# 06_Data_IN_OUT.net
KiCad netlist of a schematic drawn in Altium Designer
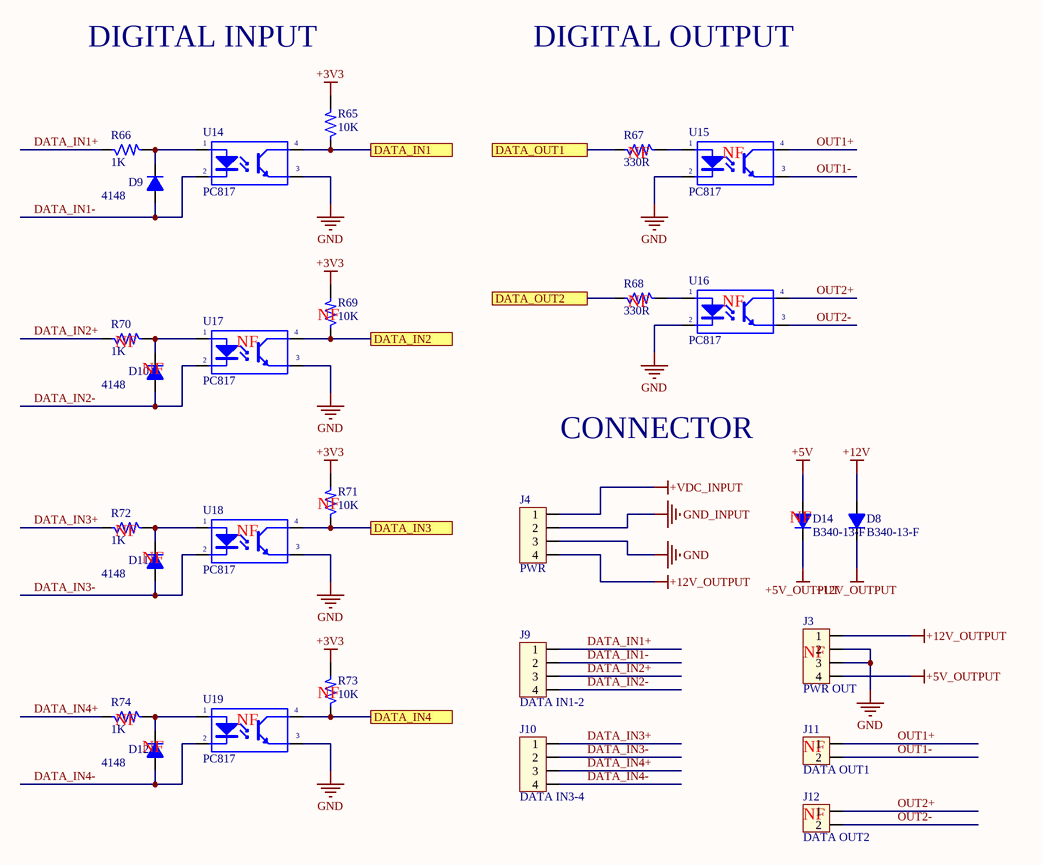
[diagram p0: [06] Data IN_OUT.SchDoc]

(export (version "E")
  (design (tool "Eeschema 10.0.6"))
  (components
    (comp (ref "D8")
      (value "B340-13-F")
      (footprint "DO-214AB SMA")
      (description "Diode 1A")
      (libsource (lib "khapham") (part "D1A"))
    )
    (comp (ref "D9")
      (value "4148")
      (footprint "DO-4148 SMD")
      (description "Diode 1A")
      (libsource (lib "khapham") (part "D1A"))
    )
    (comp (ref "D10")
      (value "4148")
      (footprint "DO-4148 SMD")
      (description "Diode 1A")
      (libsource (lib "khapham") (part "D1A"))
    )
    (comp (ref "D11")
      (value "4148")
      (footprint "DO-4148 SMD")
      (description "Diode 1A")
      (libsource (lib "khapham") (part "D1A"))
    )
    (comp (ref "D12")
      (value "4148")
      (footprint "DO-4148 SMD")
      (description "Diode 1A")
      (libsource (lib "khapham") (part "D1A"))
    )
    (comp (ref "D14")
      (value "B340-13-F")
      (footprint "DO-214AB SMA")
      (description "Diode 1A")
      (libsource (lib "khapham") (part "D1A"))
    )
    (comp (ref "J3")
      (value "PWR OUT")
      (footprint "CON_2.54mm_4")
      (description "Connector 4")
      (libsource (lib "khapham") (part "Con4"))
    )
    (comp (ref "J4")
      (value "PWR")
      (footprint "Hed4V_3.96")
      (description "Header 4 (Green)")
      (libsource (lib "khapham") (part "Hed4"))
    )
    (comp (ref "J9")
      (value "DATA IN1-2")
      (footprint "CON_2.54mm_4")
      (description "Connector 4")
      (libsource (lib "khapham") (part "Con4"))
    )
    (comp (ref "J10")
      (value "DATA IN3-4")
      (footprint "CON_2.54mm_4")
      (description "Connector 4")
      (libsource (lib "khapham") (part "Con4"))
    )
    (comp (ref "J11")
      (value "DATA OUT1")
      (footprint "CON_2.54mm_2")
      (description "Connector 2")
      (libsource (lib "khapham") (part "Con2"))
    )
    (comp (ref "J12")
      (value "DATA OUT2")
      (footprint "CON_2.54mm_2")
      (description "Connector 2")
      (libsource (lib "khapham") (part "Con2"))
    )
    (comp (ref "R65")
      (value "10K")
      (footprint "R0603 -SMT")
      (description "Resistor SMD")
      (libsource (lib "khapham") (part "RM"))
    )
    (comp (ref "R66")
      (value "1K")
      (footprint "R0603 -SMT")
      (description "Resistor SMD")
      (libsource (lib "khapham") (part "RM"))
    )
    (comp (ref "R67")
      (value "330R")
      (footprint "R0603 -SMT")
      (description "Resistor SMD")
      (libsource (lib "khapham") (part "RM"))
    )
    (comp (ref "R68")
      (value "330R")
      (footprint "R0603 -SMT")
      (description "Resistor SMD")
      (libsource (lib "khapham") (part "RM"))
    )
    (comp (ref "R69")
      (value "10K")
      (footprint "R0603 -SMT")
      (description "Resistor SMD")
      (libsource (lib "khapham") (part "RM"))
    )
    (comp (ref "R70")
      (value "1K")
      (footprint "R0603 -SMT")
      (description "Resistor SMD")
      (libsource (lib "khapham") (part "RM"))
    )
    (comp (ref "R71")
      (value "10K")
      (footprint "R0603 -SMT")
      (description "Resistor SMD")
      (libsource (lib "khapham") (part "RM"))
    )
    (comp (ref "R72")
      (value "1K")
      (footprint "R0603 -SMT")
      (description "Resistor SMD")
      (libsource (lib "khapham") (part "RM"))
    )
    (comp (ref "R73")
      (value "10K")
      (footprint "R0603 -SMT")
      (description "Resistor SMD")
      (libsource (lib "khapham") (part "RM"))
    )
    (comp (ref "R74")
      (value "1K")
      (footprint "R0603 -SMT")
      (description "Resistor SMD")
      (libsource (lib "khapham") (part "RM"))
    )
    (comp (ref "U14")
      (value "PC817")
      (footprint "DIP4/W0.3")
      (description "Single Opto")
      (libsource (lib "khapham") (part "PC817"))
    )
    (comp (ref "U15")
      (value "PC817")
      (footprint "DIP4/W0.3")
      (description "Single Opto")
      (libsource (lib "khapham") (part "PC817"))
    )
    (comp (ref "U16")
      (value "PC817")
      (footprint "DIP4/W0.3")
      (description "Single Opto")
      (libsource (lib "khapham") (part "PC817"))
    )
    (comp (ref "U17")
      (value "PC817")
      (footprint "DIP4/W0.3")
      (description "Single Opto")
      (libsource (lib "khapham") (part "PC817"))
    )
    (comp (ref "U18")
      (value "PC817")
      (footprint "DIP4/W0.3")
      (description "Single Opto")
      (libsource (lib "khapham") (part "PC817"))
    )
    (comp (ref "U19")
      (value "PC817")
      (footprint "DIP4/W0.3")
      (description "Single Opto")
      (libsource (lib "khapham") (part "PC817"))
    )
  )
  (nets
    (net (code "1") (name "+3V3") (class "Default")
      (node (ref "R65") (pin "2") (pinfunction "2_2") (pintype "passive"))
      (node (ref "R69") (pin "2") (pinfunction "2_2") (pintype "passive"))
      (node (ref "R71") (pin "2") (pinfunction "2_2") (pintype "passive"))
      (node (ref "R73") (pin "2") (pinfunction "2_2") (pintype "passive"))
    )
    (net (code "2") (name "+5V") (class "Default")
      (node (ref "D14") (pin "1") (pinfunction "A_1") (pintype "passive"))
    )
    (net (code "3") (name "+5V_OUTPUT") (class "Default")
      (node (ref "D14") (pin "2") (pinfunction "K_2") (pintype "passive"))
      (node (ref "J3") (pin "4") (pinfunction "4_4") (pintype "passive"))
    )
    (net (code "4") (name "+12V") (class "Default")
      (node (ref "D8") (pin "1") (pinfunction "A_1") (pintype "passive"))
    )
    (net (code "5") (name "+12V_OUTPUT") (class "Default")
      (node (ref "D8") (pin "2") (pinfunction "K_2") (pintype "passive"))
      (node (ref "J3") (pin "1") (pinfunction "1_1") (pintype "passive"))
      (node (ref "J4") (pin "4") (pinfunction "4_4") (pintype "passive"))
    )
    (net (code "6") (name "+VDC_INPUT") (class "Default")
      (node (ref "J4") (pin "1") (pinfunction "1_1") (pintype "passive"))
    )
    (net (code "7") (name "/DATA_IN1") (class "Default")
      (node (ref "R65") (pin "1") (pinfunction "1_1") (pintype "passive"))
      (node (ref "U14") (pin "4") (pinfunction "C_4") (pintype "passive"))
    )
    (net (code "8") (name "/DATA_IN1+") (class "Default")
      (node (ref "J9") (pin "1") (pinfunction "1_1") (pintype "passive"))
      (node (ref "R66") (pin "1") (pinfunction "1_1") (pintype "passive"))
    )
    (net (code "9") (name "/DATA_IN1-") (class "Default")
      (node (ref "D9") (pin "1") (pinfunction "A_1") (pintype "passive"))
      (node (ref "J9") (pin "2") (pinfunction "2_2") (pintype "passive"))
      (node (ref "U14") (pin "2") (pinfunction "K_2") (pintype "passive"))
    )
    (net (code "10") (name "/DATA_IN2") (class "Default")
      (node (ref "R69") (pin "1") (pinfunction "1_1") (pintype "passive"))
      (node (ref "U17") (pin "4") (pinfunction "C_4") (pintype "passive"))
    )
    (net (code "11") (name "/DATA_IN2+") (class "Default")
      (node (ref "J9") (pin "3") (pinfunction "3_3") (pintype "passive"))
      (node (ref "R70") (pin "1") (pinfunction "1_1") (pintype "passive"))
    )
    (net (code "12") (name "/DATA_IN2-") (class "Default")
      (node (ref "D10") (pin "1") (pinfunction "A_1") (pintype "passive"))
      (node (ref "J9") (pin "4") (pinfunction "4_4") (pintype "passive"))
      (node (ref "U17") (pin "2") (pinfunction "K_2") (pintype "passive"))
    )
    (net (code "13") (name "/DATA_IN3") (class "Default")
      (node (ref "R71") (pin "1") (pinfunction "1_1") (pintype "passive"))
      (node (ref "U18") (pin "4") (pinfunction "C_4") (pintype "passive"))
    )
    (net (code "14") (name "/DATA_IN3+") (class "Default")
      (node (ref "J10") (pin "1") (pinfunction "1_1") (pintype "passive"))
      (node (ref "R72") (pin "1") (pinfunction "1_1") (pintype "passive"))
    )
    (net (code "15") (name "/DATA_IN3-") (class "Default")
      (node (ref "D11") (pin "1") (pinfunction "A_1") (pintype "passive"))
      (node (ref "J10") (pin "2") (pinfunction "2_2") (pintype "passive"))
      (node (ref "U18") (pin "2") (pinfunction "K_2") (pintype "passive"))
    )
    (net (code "16") (name "/DATA_IN4") (class "Default")
      (node (ref "R73") (pin "1") (pinfunction "1_1") (pintype "passive"))
      (node (ref "U19") (pin "4") (pinfunction "C_4") (pintype "passive"))
    )
    (net (code "17") (name "/DATA_IN4+") (class "Default")
      (node (ref "J10") (pin "3") (pinfunction "3_3") (pintype "passive"))
      (node (ref "R74") (pin "1") (pinfunction "1_1") (pintype "passive"))
    )
    (net (code "18") (name "/DATA_IN4-") (class "Default")
      (node (ref "D12") (pin "1") (pinfunction "A_1") (pintype "passive"))
      (node (ref "J10") (pin "4") (pinfunction "4_4") (pintype "passive"))
      (node (ref "U19") (pin "2") (pinfunction "K_2") (pintype "passive"))
    )
    (net (code "19") (name "/DATA_OUT1") (class "Default")
      (node (ref "R67") (pin "1") (pinfunction "1_1") (pintype "passive"))
    )
    (net (code "20") (name "/DATA_OUT2") (class "Default")
      (node (ref "R68") (pin "1") (pinfunction "1_1") (pintype "passive"))
    )
    (net (code "21") (name "/OUT1+") (class "Default")
      (node (ref "J11") (pin "1") (pinfunction "1_1") (pintype "passive"))
      (node (ref "U15") (pin "4") (pinfunction "C_4") (pintype "passive"))
    )
    (net (code "22") (name "/OUT1-") (class "Default")
      (node (ref "J11") (pin "2") (pinfunction "2_2") (pintype "passive"))
      (node (ref "U15") (pin "3") (pinfunction "E_3") (pintype "passive"))
    )
    (net (code "23") (name "/OUT2+") (class "Default")
      (node (ref "J12") (pin "1") (pinfunction "1_1") (pintype "passive"))
      (node (ref "U16") (pin "4") (pinfunction "C_4") (pintype "passive"))
    )
    (net (code "24") (name "/OUT2-") (class "Default")
      (node (ref "J12") (pin "2") (pinfunction "2_2") (pintype "passive"))
      (node (ref "U16") (pin "3") (pinfunction "E_3") (pintype "passive"))
    )
    (net (code "25") (name "GND") (class "Default")
      (node (ref "J3") (pin "2") (pinfunction "2_2") (pintype "passive"))
      (node (ref "J3") (pin "3") (pinfunction "3_3") (pintype "passive"))
      (node (ref "J4") (pin "3") (pinfunction "3_3") (pintype "passive"))
      (node (ref "U14") (pin "3") (pinfunction "E_3") (pintype "passive"))
      (node (ref "U15") (pin "2") (pinfunction "K_2") (pintype "passive"))
      (node (ref "U16") (pin "2") (pinfunction "K_2") (pintype "passive"))
      (node (ref "U17") (pin "3") (pinfunction "E_3") (pintype "passive"))
      (node (ref "U18") (pin "3") (pinfunction "E_3") (pintype "passive"))
      (node (ref "U19") (pin "3") (pinfunction "E_3") (pintype "passive"))
    )
    (net (code "26") (name "GND_INPUT") (class "Default")
      (node (ref "J4") (pin "2") (pinfunction "2_2") (pintype "passive"))
    )
    (net (code "27") (name "Net-(D9-K)") (class "Default")
      (node (ref "D9") (pin "2") (pinfunction "K_2") (pintype "passive"))
      (node (ref "R66") (pin "2") (pinfunction "2_2") (pintype "passive"))
      (node (ref "U14") (pin "1") (pinfunction "A_1") (pintype "passive"))
    )
    (net (code "28") (name "Net-(D10-K)") (class "Default")
      (node (ref "D10") (pin "2") (pinfunction "K_2") (pintype "passive"))
      (node (ref "R70") (pin "2") (pinfunction "2_2") (pintype "passive"))
      (node (ref "U17") (pin "1") (pinfunction "A_1") (pintype "passive"))
    )
    (net (code "29") (name "Net-(D11-K)") (class "Default")
      (node (ref "D11") (pin "2") (pinfunction "K_2") (pintype "passive"))
      (node (ref "R72") (pin "2") (pinfunction "2_2") (pintype "passive"))
      (node (ref "U18") (pin "1") (pinfunction "A_1") (pintype "passive"))
    )
    (net (code "30") (name "Net-(D12-K)") (class "Default")
      (node (ref "D12") (pin "2") (pinfunction "K_2") (pintype "passive"))
      (node (ref "R74") (pin "2") (pinfunction "2_2") (pintype "passive"))
      (node (ref "U19") (pin "1") (pinfunction "A_1") (pintype "passive"))
    )
    (net (code "31") (name "Net-(U15-A)") (class "Default")
      (node (ref "R67") (pin "2") (pinfunction "2_2") (pintype "passive"))
      (node (ref "U15") (pin "1") (pinfunction "A_1") (pintype "passive"))
    )
    (net (code "32") (name "Net-(U16-A)") (class "Default")
      (node (ref "R68") (pin "2") (pinfunction "2_2") (pintype "passive"))
      (node (ref "U16") (pin "1") (pinfunction "A_1") (pintype "passive"))
    )
  )
)
